# alarm_clock.net
KiCad netlist of a schematic drawn in EAGLE
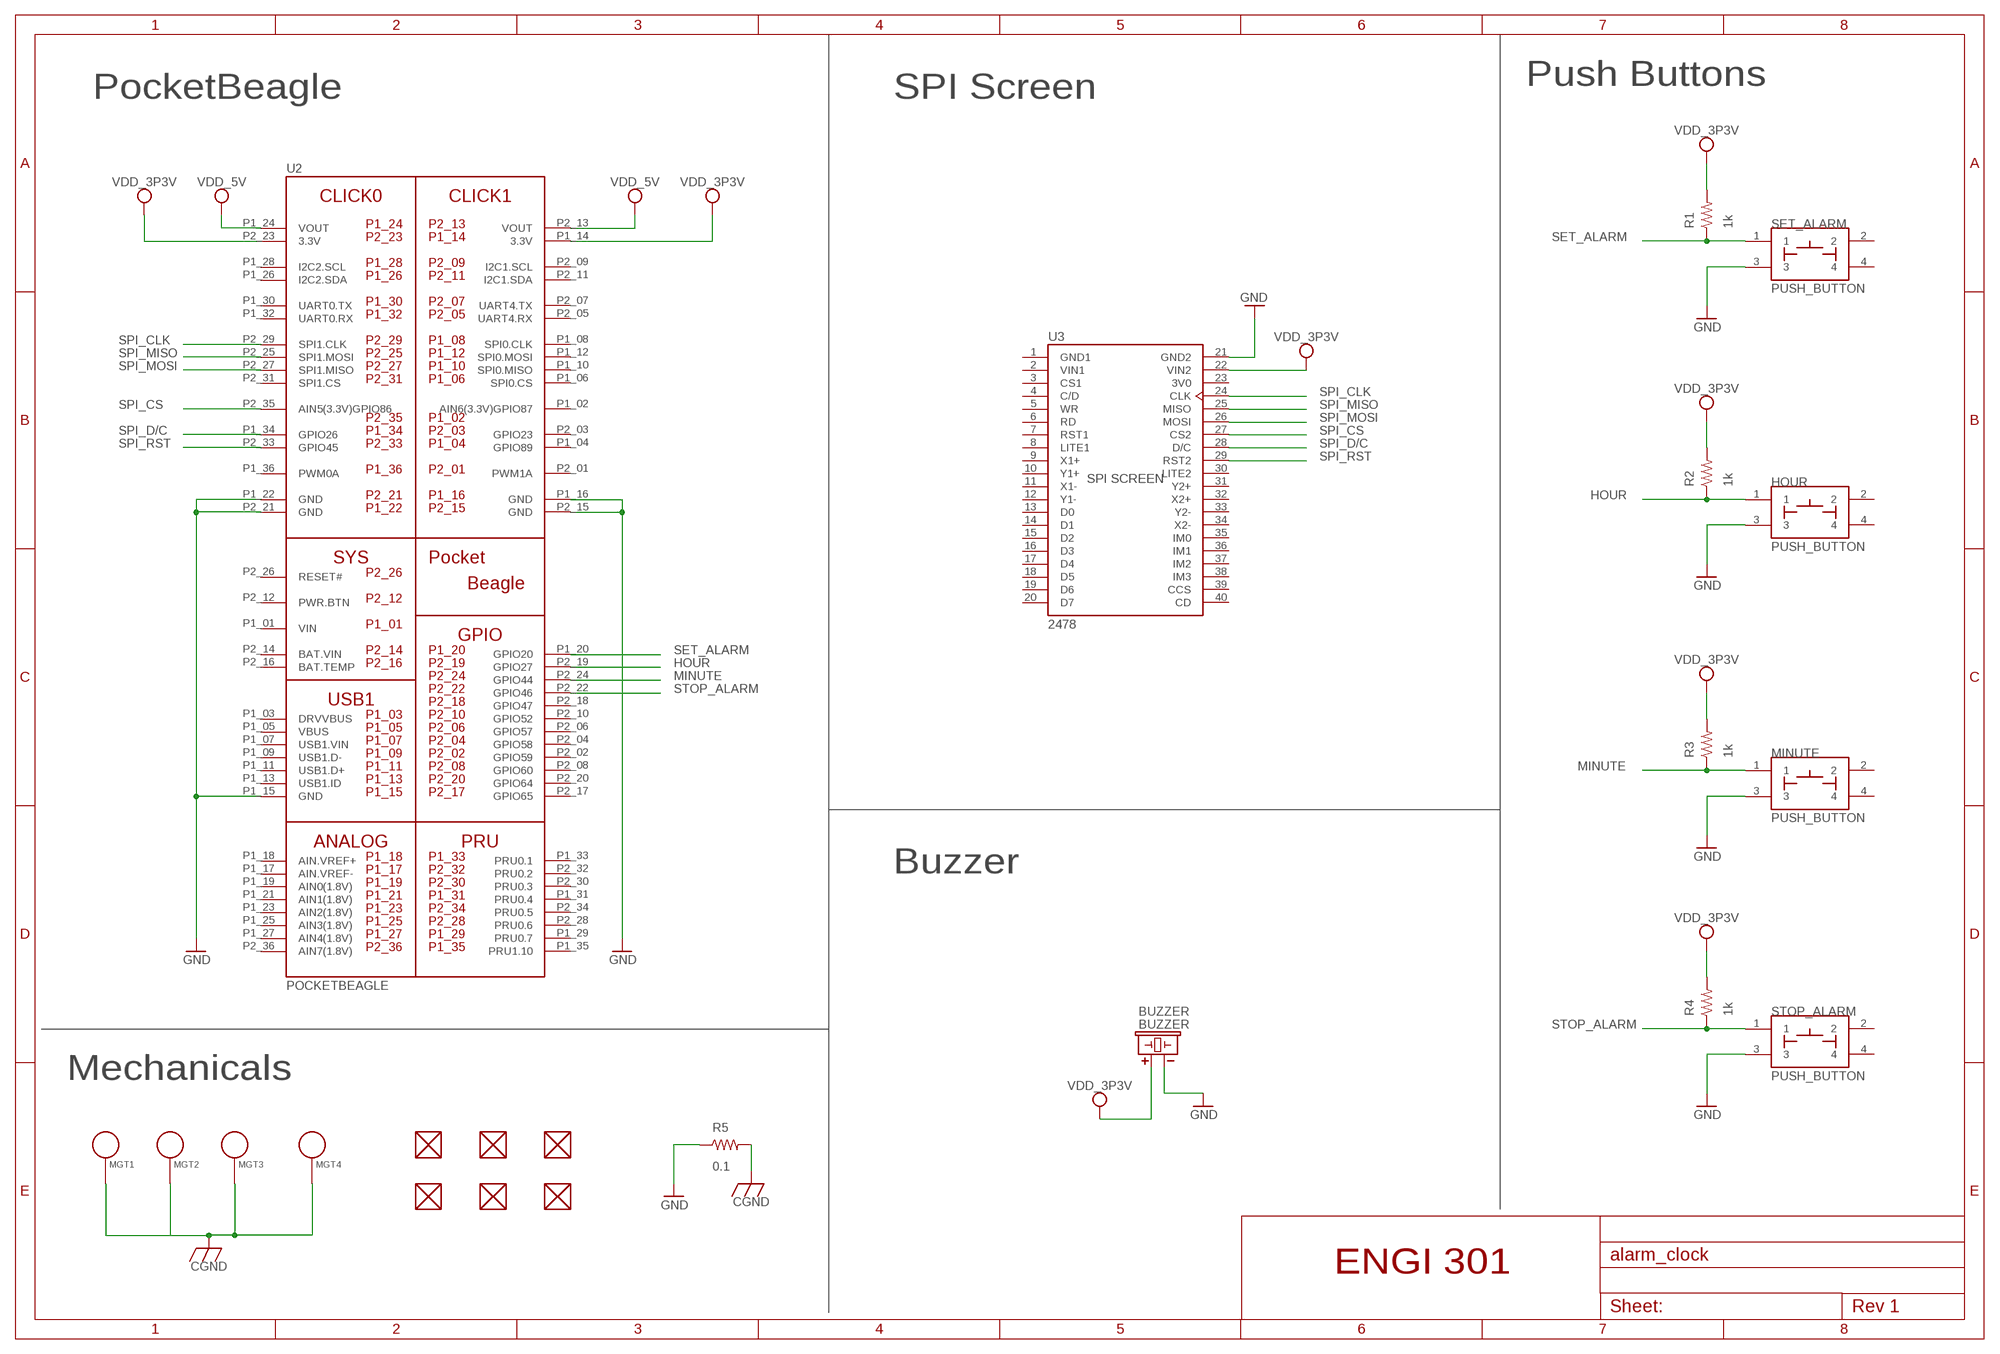
[diagram p0: schematic, sheet 1]

(export (version "E")
  (design (tool "Eeschema 10.0.6"))
  (components
    (comp (ref "BUZZER")
      (value "BUZZER")
      (footprint "eagle-import:BUZZER_6.5MM")
      (libsource (lib "eagle-import") (part "BUZZER"))
    )
    (comp (ref "FUD1")
      (value "FIDUCIAL")
      (footprint "eagle-import:FIDUCIAL_40MIL")
      (libsource (lib "eagle-import") (part "FIDUCIAL"))
    )
    (comp (ref "FUD2")
      (value "FIDUCIAL")
      (footprint "eagle-import:FIDUCIAL_40MIL")
      (libsource (lib "eagle-import") (part "FIDUCIAL"))
    )
    (comp (ref "FUD3")
      (value "FIDUCIAL")
      (footprint "eagle-import:FIDUCIAL_40MIL")
      (libsource (lib "eagle-import") (part "FIDUCIAL"))
    )
    (comp (ref "FUD4")
      (value "FIDUCIAL")
      (footprint "eagle-import:FIDUCIAL_40MIL")
      (libsource (lib "eagle-import") (part "FIDUCIAL"))
    )
    (comp (ref "FUD5")
      (value "FIDUCIAL")
      (footprint "eagle-import:FIDUCIAL_40MIL")
      (libsource (lib "eagle-import") (part "FIDUCIAL"))
    )
    (comp (ref "FUD6")
      (value "FIDUCIAL")
      (footprint "eagle-import:FIDUCIAL_40MIL")
      (libsource (lib "eagle-import") (part "FIDUCIAL"))
    )
    (comp (ref "HOUR")
      (value "PUSH_BUTTON")
      (footprint "eagle-import:BUTTON_12.5MM")
      (libsource (lib "eagle-import") (part "PUSH_BUTTON"))
    )
    (comp (ref "MGT1")
      (value "MOUNTING_HOLE")
      (footprint "eagle-import:MOUNTING_HOLE")
      (libsource (lib "eagle-import") (part "MOUNTING_HOLE"))
    )
    (comp (ref "MGT2")
      (value "MOUNTING_HOLE")
      (footprint "eagle-import:MOUNTING_HOLE")
      (libsource (lib "eagle-import") (part "MOUNTING_HOLE"))
    )
    (comp (ref "MGT3")
      (value "MOUNTING_HOLE")
      (footprint "eagle-import:MOUNTING_HOLE")
      (libsource (lib "eagle-import") (part "MOUNTING_HOLE"))
    )
    (comp (ref "MGT4")
      (value "MOUNTING_HOLE")
      (footprint "eagle-import:MOUNTING_HOLE")
      (libsource (lib "eagle-import") (part "MOUNTING_HOLE"))
    )
    (comp (ref "MINUTE")
      (value "PUSH_BUTTON")
      (footprint "eagle-import:BUTTON_12.5MM")
      (libsource (lib "eagle-import") (part "PUSH_BUTTON"))
    )
    (comp (ref "R1")
      (value "1k")
      (footprint "eagle-import:R0603")
      (libsource (lib "eagle-import") (part "combo_lock_R_R0603"))
    )
    (comp (ref "R2")
      (value "1k")
      (footprint "eagle-import:R0603")
      (libsource (lib "eagle-import") (part "combo_lock_R_R0603"))
    )
    (comp (ref "R3")
      (value "1k")
      (footprint "eagle-import:R0603")
      (libsource (lib "eagle-import") (part "combo_lock_R_R0603"))
    )
    (comp (ref "R4")
      (value "1k")
      (footprint "eagle-import:R0603")
      (libsource (lib "eagle-import") (part "combo_lock_R_R0603"))
    )
    (comp (ref "R5")
      (value "0.1")
      (footprint "eagle-import:R0402")
      (libsource (lib "eagle-import") (part "R_R0402"))
    )
    (comp (ref "SET_ALARM")
      (value "PUSH_BUTTON")
      (footprint "eagle-import:BUTTON_12.5MM")
      (libsource (lib "eagle-import") (part "PUSH_BUTTON"))
    )
    (comp (ref "STOP_ALARM")
      (value "PUSH_BUTTON")
      (footprint "eagle-import:BUTTON_12.5MM")
      (libsource (lib "eagle-import") (part "PUSH_BUTTON"))
    )
    (comp (ref "U2")
      (value "POCKETBEAGLE")
      (footprint "eagle-import:POCKETBEAGLE")
      (libsource (lib "eagle-import") (part "POCKETBEAGLE"))
    )
    (comp (ref "U3")
      (value "2478")
      (footprint "eagle-import:ADAFRUIT_2478")
      (fields (field (name "MF") "Adafruit Industries"))
      (libsource (lib "eagle-import") (part "2478"))
    )
  )
  (nets
    (net (code "1") (name "/BAT.VIN") (class "Default")
      (node (ref "U2") (pin "P2_14") (pinfunction "BAT.VIN_P2_14") (pintype "power_in"))
    )
    (net (code "2") (name "/GND1") (class "Default")
      (node (ref "U3") (pin "1") (pinfunction "GND1_1") (pintype "power_in"))
    )
    (net (code "3") (name "/HOUR") (class "Default")
      (node (ref "HOUR") (pin "1") (pinfunction "1_1") (pintype "bidirectional"))
      (node (ref "R2") (pin "1") (pinfunction "1_1") (pintype "passive"))
      (node (ref "U2") (pin "P2_19") (pinfunction "GPIO27_P2_19") (pintype "bidirectional"))
    )
    (net (code "4") (name "/MINUTE") (class "Default")
      (node (ref "MINUTE") (pin "1") (pinfunction "1_1") (pintype "bidirectional"))
      (node (ref "R3") (pin "1") (pinfunction "1_1") (pintype "passive"))
      (node (ref "U2") (pin "P2_24") (pinfunction "GPIO44_P2_24") (pintype "bidirectional"))
    )
    (net (code "5") (name "/SET_ALARM") (class "Default")
      (node (ref "R1") (pin "1") (pinfunction "1_1") (pintype "passive"))
      (node (ref "SET_ALARM") (pin "1") (pinfunction "1_1") (pintype "bidirectional"))
      (node (ref "U2") (pin "P1_20") (pinfunction "GPIO20_P1_20") (pintype "bidirectional"))
    )
    (net (code "6") (name "/SPI_CLK") (class "Default")
      (node (ref "U2") (pin "P2_29") (pinfunction "SPI1.CLK_P2_29") (pintype "bidirectional"))
      (node (ref "U3") (pin "24") (pinfunction "CLK_24") (pintype "input"))
    )
    (net (code "7") (name "/SPI_CS") (class "Default")
      (node (ref "U2") (pin "P2_35") (pinfunction "AIN5(3.3V)GPIO86_P2_35") (pintype "bidirectional"))
      (node (ref "U3") (pin "27") (pinfunction "CS2_27") (pintype "input"))
    )
    (net (code "8") (name "/SPI_D{slash}C") (class "Default")
      (node (ref "U2") (pin "P1_34") (pinfunction "GPIO26_P1_34") (pintype "bidirectional"))
      (node (ref "U3") (pin "28") (pinfunction "D/C_28") (pintype "input"))
    )
    (net (code "9") (name "/SPI_MISO") (class "Default")
      (node (ref "U2") (pin "P2_25") (pinfunction "SPI1.MOSI_P2_25") (pintype "bidirectional"))
      (node (ref "U3") (pin "25") (pinfunction "MISO_25") (pintype "output"))
    )
    (net (code "10") (name "/SPI_MOSI") (class "Default")
      (node (ref "U2") (pin "P2_27") (pinfunction "SPI1.MISO_P2_27") (pintype "bidirectional"))
      (node (ref "U3") (pin "26") (pinfunction "MOSI_26") (pintype "input"))
    )
    (net (code "11") (name "/SPI_RST") (class "Default")
      (node (ref "U2") (pin "P2_33") (pinfunction "GPIO45_P2_33") (pintype "bidirectional"))
      (node (ref "U3") (pin "29") (pinfunction "RST2_29") (pintype "input"))
    )
    (net (code "12") (name "/STOP_ALARM") (class "Default")
      (node (ref "R4") (pin "1") (pinfunction "1_1") (pintype "passive"))
      (node (ref "STOP_ALARM") (pin "1") (pinfunction "1_1") (pintype "bidirectional"))
      (node (ref "U2") (pin "P2_22") (pinfunction "GPIO46_P2_22") (pintype "bidirectional"))
    )
    (net (code "13") (name "/VIN") (class "Default")
      (node (ref "U2") (pin "P1_01") (pinfunction "VIN_P1_01") (pintype "power_in"))
    )
    (net (code "14") (name "/VIN1") (class "Default")
      (node (ref "U3") (pin "2") (pinfunction "VIN1_2") (pintype "power_in"))
    )
    (net (code "15") (name "CGND") (class "Default")
      (node (ref "MGT1") (pin "P$1") (pinfunction "P$1_P$1") (pintype "bidirectional"))
      (node (ref "MGT2") (pin "P$1") (pinfunction "P$1_P$1") (pintype "bidirectional"))
      (node (ref "MGT3") (pin "P$1") (pinfunction "P$1_P$1") (pintype "bidirectional"))
      (node (ref "MGT4") (pin "P$1") (pinfunction "P$1_P$1") (pintype "bidirectional"))
      (node (ref "R5") (pin "2") (pinfunction "2_2") (pintype "passive"))
    )
    (net (code "16") (name "GND") (class "Default")
      (node (ref "BUZZER") (pin "-") (pinfunction "-_-") (pintype "passive"))
      (node (ref "HOUR") (pin "3") (pinfunction "3_3") (pintype "bidirectional"))
      (node (ref "MINUTE") (pin "3") (pinfunction "3_3") (pintype "bidirectional"))
      (node (ref "R5") (pin "1") (pinfunction "1_1") (pintype "passive"))
      (node (ref "SET_ALARM") (pin "3") (pinfunction "3_3") (pintype "bidirectional"))
      (node (ref "STOP_ALARM") (pin "3") (pinfunction "3_3") (pintype "bidirectional"))
      (node (ref "U2") (pin "P1_15") (pinfunction "GND_P1_15") (pintype "bidirectional"))
      (node (ref "U2") (pin "P1_16") (pinfunction "GND_P1_16") (pintype "power_in"))
      (node (ref "U2") (pin "P1_22") (pinfunction "GND_P1_22") (pintype "power_in"))
      (node (ref "U2") (pin "P2_15") (pinfunction "GND_P2_15") (pintype "power_in"))
      (node (ref "U2") (pin "P2_21") (pinfunction "GND_P2_21") (pintype "power_in"))
      (node (ref "U3") (pin "21") (pinfunction "GND2_21") (pintype "power_in"))
    )
    (net (code "17") (name "VDD_3P3V") (class "Default")
      (node (ref "BUZZER") (pin "+") (pinfunction "+_+") (pintype "passive"))
      (node (ref "R1") (pin "2") (pinfunction "2_2") (pintype "passive"))
      (node (ref "R2") (pin "2") (pinfunction "2_2") (pintype "passive"))
      (node (ref "R3") (pin "2") (pinfunction "2_2") (pintype "passive"))
      (node (ref "R4") (pin "2") (pinfunction "2_2") (pintype "passive"))
      (node (ref "U2") (pin "P1_14") (pinfunction "3.3V_P1_14") (pintype "power_in"))
      (node (ref "U2") (pin "P2_23") (pinfunction "3.3V_P2_23") (pintype "power_in"))
      (node (ref "U3") (pin "22") (pinfunction "VIN2_22") (pintype "power_in"))
    )
    (net (code "18") (name "VDD_5V") (class "Default")
      (node (ref "U2") (pin "P1_24") (pinfunction "VOUT_P1_24") (pintype "power_in"))
      (node (ref "U2") (pin "P2_13") (pinfunction "VOUT_P2_13") (pintype "power_in"))
    )
    (net (code "19") (name "unconnected-(FUD1-PadP$1)") (class "Default")
      (node (ref "FUD1") (pin "P$1") (pinfunction "P$1_P$1") (pintype "no_connect"))
    )
    (net (code "20") (name "unconnected-(FUD2-PadP$1)") (class "Default")
      (node (ref "FUD2") (pin "P$1") (pinfunction "P$1_P$1") (pintype "no_connect"))
    )
    (net (code "21") (name "unconnected-(FUD3-PadP$1)") (class "Default")
      (node (ref "FUD3") (pin "P$1") (pinfunction "P$1_P$1") (pintype "no_connect"))
    )
    (net (code "22") (name "unconnected-(FUD4-PadP$1)") (class "Default")
      (node (ref "FUD4") (pin "P$1") (pinfunction "P$1_P$1") (pintype "no_connect"))
    )
    (net (code "23") (name "unconnected-(FUD5-PadP$1)") (class "Default")
      (node (ref "FUD5") (pin "P$1") (pinfunction "P$1_P$1") (pintype "no_connect"))
    )
    (net (code "24") (name "unconnected-(FUD6-PadP$1)") (class "Default")
      (node (ref "FUD6") (pin "P$1") (pinfunction "P$1_P$1") (pintype "no_connect"))
    )
    (net (code "25") (name "unconnected-(HOUR-Pad2)") (class "Default")
      (node (ref "HOUR") (pin "2") (pinfunction "2_2") (pintype "bidirectional"))
    )
    (net (code "26") (name "unconnected-(HOUR-Pad4)") (class "Default")
      (node (ref "HOUR") (pin "4") (pinfunction "4_4") (pintype "bidirectional"))
    )
    (net (code "27") (name "unconnected-(MINUTE-Pad2)") (class "Default")
      (node (ref "MINUTE") (pin "2") (pinfunction "2_2") (pintype "bidirectional"))
    )
    (net (code "28") (name "unconnected-(MINUTE-Pad4)") (class "Default")
      (node (ref "MINUTE") (pin "4") (pinfunction "4_4") (pintype "bidirectional"))
    )
    (net (code "29") (name "unconnected-(SET_ALARM-Pad2)") (class "Default")
      (node (ref "SET_ALARM") (pin "2") (pinfunction "2_2") (pintype "bidirectional"))
    )
    (net (code "30") (name "unconnected-(SET_ALARM-Pad4)") (class "Default")
      (node (ref "SET_ALARM") (pin "4") (pinfunction "4_4") (pintype "bidirectional"))
    )
    (net (code "31") (name "unconnected-(STOP_ALARM-Pad2)") (class "Default")
      (node (ref "STOP_ALARM") (pin "2") (pinfunction "2_2") (pintype "bidirectional"))
    )
    (net (code "32") (name "unconnected-(STOP_ALARM-Pad4)") (class "Default")
      (node (ref "STOP_ALARM") (pin "4") (pinfunction "4_4") (pintype "bidirectional"))
    )
    (net (code "33") (name "unconnected-(U2-AIN.VREF+-PadP1_18)") (class "Default")
      (node (ref "U2") (pin "P1_18") (pinfunction "AIN.VREF+_P1_18") (pintype "input"))
    )
    (net (code "34") (name "unconnected-(U2-AIN.VREF--PadP1_17)") (class "Default")
      (node (ref "U2") (pin "P1_17") (pinfunction "AIN.VREF-_P1_17") (pintype "input"))
    )
    (net (code "35") (name "unconnected-(U2-AIN0(1.8V)-PadP1_19)") (class "Default")
      (node (ref "U2") (pin "P1_19") (pinfunction "AIN0(1.8V)_P1_19") (pintype "input"))
    )
    (net (code "36") (name "unconnected-(U2-AIN1(1.8V)-PadP1_21)") (class "Default")
      (node (ref "U2") (pin "P1_21") (pinfunction "AIN1(1.8V)_P1_21") (pintype "input"))
    )
    (net (code "37") (name "unconnected-(U2-AIN2(1.8V)-PadP1_23)") (class "Default")
      (node (ref "U2") (pin "P1_23") (pinfunction "AIN2(1.8V)_P1_23") (pintype "input"))
    )
    (net (code "38") (name "unconnected-(U2-AIN3(1.8V)-PadP1_25)") (class "Default")
      (node (ref "U2") (pin "P1_25") (pinfunction "AIN3(1.8V)_P1_25") (pintype "input"))
    )
    (net (code "39") (name "unconnected-(U2-AIN4(1.8V)-PadP1_27)") (class "Default")
      (node (ref "U2") (pin "P1_27") (pinfunction "AIN4(1.8V)_P1_27") (pintype "input"))
    )
    (net (code "40") (name "unconnected-(U2-AIN6(3.3V)GPIO87-PadP1_02)") (class "Default")
      (node (ref "U2") (pin "P1_02") (pinfunction "AIN6(3.3V)GPIO87_P1_02") (pintype "bidirectional"))
    )
    (net (code "41") (name "unconnected-(U2-AIN7(1.8V)-PadP2_36)") (class "Default")
      (node (ref "U2") (pin "P2_36") (pinfunction "AIN7(1.8V)_P2_36") (pintype "input"))
    )
    (net (code "42") (name "unconnected-(U2-BAT.TEMP-PadP2_16)") (class "Default")
      (node (ref "U2") (pin "P2_16") (pinfunction "BAT.TEMP_P2_16") (pintype "input"))
    )
    (net (code "43") (name "unconnected-(U2-DRVVBUS-PadP1_03)") (class "Default")
      (node (ref "U2") (pin "P1_03") (pinfunction "DRVVBUS_P1_03") (pintype "bidirectional"))
    )
    (net (code "44") (name "unconnected-(U2-GPIO23-PadP2_03)") (class "Default")
      (node (ref "U2") (pin "P2_03") (pinfunction "GPIO23_P2_03") (pintype "bidirectional"))
    )
    (net (code "45") (name "unconnected-(U2-GPIO47-PadP2_18)") (class "Default")
      (node (ref "U2") (pin "P2_18") (pinfunction "GPIO47_P2_18") (pintype "bidirectional"))
    )
    (net (code "46") (name "unconnected-(U2-GPIO52-PadP2_10)") (class "Default")
      (node (ref "U2") (pin "P2_10") (pinfunction "GPIO52_P2_10") (pintype "bidirectional"))
    )
    (net (code "47") (name "unconnected-(U2-GPIO57-PadP2_06)") (class "Default")
      (node (ref "U2") (pin "P2_06") (pinfunction "GPIO57_P2_06") (pintype "bidirectional"))
    )
    (net (code "48") (name "unconnected-(U2-GPIO58-PadP2_04)") (class "Default")
      (node (ref "U2") (pin "P2_04") (pinfunction "GPIO58_P2_04") (pintype "bidirectional"))
    )
    (net (code "49") (name "unconnected-(U2-GPIO59-PadP2_02)") (class "Default")
      (node (ref "U2") (pin "P2_02") (pinfunction "GPIO59_P2_02") (pintype "bidirectional"))
    )
    (net (code "50") (name "unconnected-(U2-GPIO60-PadP2_08)") (class "Default")
      (node (ref "U2") (pin "P2_08") (pinfunction "GPIO60_P2_08") (pintype "bidirectional"))
    )
    (net (code "51") (name "unconnected-(U2-GPIO64-PadP2_20)") (class "Default")
      (node (ref "U2") (pin "P2_20") (pinfunction "GPIO64_P2_20") (pintype "bidirectional"))
    )
    (net (code "52") (name "unconnected-(U2-GPIO65-PadP2_17)") (class "Default")
      (node (ref "U2") (pin "P2_17") (pinfunction "GPIO65_P2_17") (pintype "bidirectional"))
    )
    (net (code "53") (name "unconnected-(U2-GPIO89-PadP1_04)") (class "Default")
      (node (ref "U2") (pin "P1_04") (pinfunction "GPIO89_P1_04") (pintype "bidirectional"))
    )
    (net (code "54") (name "unconnected-(U2-I2C1.SCL-PadP2_09)") (class "Default")
      (node (ref "U2") (pin "P2_09") (pinfunction "I2C1.SCL_P2_09") (pintype "bidirectional"))
    )
    (net (code "55") (name "unconnected-(U2-I2C1.SDA-PadP2_11)") (class "Default")
      (node (ref "U2") (pin "P2_11") (pinfunction "I2C1.SDA_P2_11") (pintype "bidirectional"))
    )
    (net (code "56") (name "unconnected-(U2-I2C2.SCL-PadP1_28)") (class "Default")
      (node (ref "U2") (pin "P1_28") (pinfunction "I2C2.SCL_P1_28") (pintype "bidirectional"))
    )
    (net (code "57") (name "unconnected-(U2-I2C2.SDA-PadP1_26)") (class "Default")
      (node (ref "U2") (pin "P1_26") (pinfunction "I2C2.SDA_P1_26") (pintype "bidirectional"))
    )
    (net (code "58") (name "unconnected-(U2-PRU0.1-PadP1_33)") (class "Default")
      (node (ref "U2") (pin "P1_33") (pinfunction "PRU0.1_P1_33") (pintype "bidirectional"))
    )
    (net (code "59") (name "unconnected-(U2-PRU0.2-PadP2_32)") (class "Default")
      (node (ref "U2") (pin "P2_32") (pinfunction "PRU0.2_P2_32") (pintype "bidirectional"))
    )
    (net (code "60") (name "unconnected-(U2-PRU0.3-PadP2_30)") (class "Default")
      (node (ref "U2") (pin "P2_30") (pinfunction "PRU0.3_P2_30") (pintype "bidirectional"))
    )
    (net (code "61") (name "unconnected-(U2-PRU0.4-PadP1_31)") (class "Default")
      (node (ref "U2") (pin "P1_31") (pinfunction "PRU0.4_P1_31") (pintype "bidirectional"))
    )
    (net (code "62") (name "unconnected-(U2-PRU0.5-PadP2_34)") (class "Default")
      (node (ref "U2") (pin "P2_34") (pinfunction "PRU0.5_P2_34") (pintype "bidirectional"))
    )
    (net (code "63") (name "unconnected-(U2-PRU0.6-PadP2_28)") (class "Default")
      (node (ref "U2") (pin "P2_28") (pinfunction "PRU0.6_P2_28") (pintype "bidirectional"))
    )
    (net (code "64") (name "unconnected-(U2-PRU0.7-PadP1_29)") (class "Default")
      (node (ref "U2") (pin "P1_29") (pinfunction "PRU0.7_P1_29") (pintype "bidirectional"))
    )
    (net (code "65") (name "unconnected-(U2-PRU1.10-PadP1_35)") (class "Default")
      (node (ref "U2") (pin "P1_35") (pinfunction "PRU1.10_P1_35") (pintype "bidirectional"))
    )
    (net (code "66") (name "unconnected-(U2-PWM0A-PadP1_36)") (class "Default")
      (node (ref "U2") (pin "P1_36") (pinfunction "PWM0A_P1_36") (pintype "bidirectional"))
    )
    (net (code "67") (name "unconnected-(U2-PWM1A-PadP2_01)") (class "Default")
      (node (ref "U2") (pin "P2_01") (pinfunction "PWM1A_P2_01") (pintype "bidirectional"))
    )
    (net (code "68") (name "unconnected-(U2-PWR.BTN-PadP2_12)") (class "Default")
      (node (ref "U2") (pin "P2_12") (pinfunction "PWR.BTN_P2_12") (pintype "input"))
    )
    (net (code "69") (name "unconnected-(U2-RESET#-PadP2_26)") (class "Default")
      (node (ref "U2") (pin "P2_26") (pinfunction "RESET#_P2_26") (pintype "input"))
    )
    (net (code "70") (name "unconnected-(U2-SPI0.CLK-PadP1_08)") (class "Default")
      (node (ref "U2") (pin "P1_08") (pinfunction "SPI0.CLK_P1_08") (pintype "bidirectional"))
    )
    (net (code "71") (name "unconnected-(U2-SPI0.CS-PadP1_06)") (class "Default")
      (node (ref "U2") (pin "P1_06") (pinfunction "SPI0.CS_P1_06") (pintype "bidirectional"))
    )
    (net (code "72") (name "unconnected-(U2-SPI0.MISO-PadP1_10)") (class "Default")
      (node (ref "U2") (pin "P1_10") (pinfunction "SPI0.MISO_P1_10") (pintype "bidirectional"))
    )
    (net (code "73") (name "unconnected-(U2-SPI0.MOSI-PadP1_12)") (class "Default")
      (node (ref "U2") (pin "P1_12") (pinfunction "SPI0.MOSI_P1_12") (pintype "bidirectional"))
    )
    (net (code "74") (name "unconnected-(U2-SPI1.CS-PadP2_31)") (class "Default")
      (node (ref "U2") (pin "P2_31") (pinfunction "SPI1.CS_P2_31") (pintype "bidirectional"))
    )
    (net (code "75") (name "unconnected-(U2-UART0.RX-PadP1_32)") (class "Default")
      (node (ref "U2") (pin "P1_32") (pinfunction "UART0.RX_P1_32") (pintype "bidirectional"))
    )
    (net (code "76") (name "unconnected-(U2-UART0.TX-PadP1_30)") (class "Default")
      (node (ref "U2") (pin "P1_30") (pinfunction "UART0.TX_P1_30") (pintype "bidirectional"))
    )
    (net (code "77") (name "unconnected-(U2-UART4.RX-PadP2_05)") (class "Default")
      (node (ref "U2") (pin "P2_05") (pinfunction "UART4.RX_P2_05") (pintype "bidirectional"))
    )
    (net (code "78") (name "unconnected-(U2-UART4.TX-PadP2_07)") (class "Default")
      (node (ref "U2") (pin "P2_07") (pinfunction "UART4.TX_P2_07") (pintype "bidirectional"))
    )
    (net (code "79") (name "unconnected-(U2-USB1.D+-PadP1_11)") (class "Default")
      (node (ref "U2") (pin "P1_11") (pinfunction "USB1.D+_P1_11") (pintype "bidirectional"))
    )
    (net (code "80") (name "unconnected-(U2-USB1.D--PadP1_09)") (class "Default")
      (node (ref "U2") (pin "P1_09") (pinfunction "USB1.D-_P1_09") (pintype "bidirectional"))
    )
    (net (code "81") (name "unconnected-(U2-USB1.ID-PadP1_13)") (class "Default")
      (node (ref "U2") (pin "P1_13") (pinfunction "USB1.ID_P1_13") (pintype "bidirectional"))
    )
    (net (code "82") (name "unconnected-(U2-USB1.VIN-PadP1_07)") (class "Default")
      (node (ref "U2") (pin "P1_07") (pinfunction "USB1.VIN_P1_07") (pintype "bidirectional"))
    )
    (net (code "83") (name "unconnected-(U2-VBUS-PadP1_05)") (class "Default")
      (node (ref "U2") (pin "P1_05") (pinfunction "VBUS_P1_05") (pintype "bidirectional"))
    )
    (net (code "84") (name "unconnected-(U3-3V0-Pad23)") (class "Default")
      (node (ref "U3") (pin "23") (pinfunction "3V0_23") (pintype "output"))
    )
    (net (code "85") (name "unconnected-(U3-CCS-Pad39)") (class "Default")
      (node (ref "U3") (pin "39") (pinfunction "CCS_39") (pintype "input"))
    )
    (net (code "86") (name "unconnected-(U3-CD-Pad40)") (class "Default")
      (node (ref "U3") (pin "40") (pinfunction "CD_40") (pintype "output"))
    )
    (net (code "87") (name "unconnected-(U3-CS1-Pad3)") (class "Default")
      (node (ref "U3") (pin "3") (pinfunction "CS1_3") (pintype "input"))
    )
    (net (code "88") (name "unconnected-(U3-C{slash}D-Pad4)") (class "Default")
      (node (ref "U3") (pin "4") (pinfunction "C/D_4") (pintype "input"))
    )
    (net (code "89") (name "unconnected-(U3-D0-Pad13)") (class "Default")
      (node (ref "U3") (pin "13") (pinfunction "D0_13") (pintype "bidirectional"))
    )
    (net (code "90") (name "unconnected-(U3-D1-Pad14)") (class "Default")
      (node (ref "U3") (pin "14") (pinfunction "D1_14") (pintype "bidirectional"))
    )
    (net (code "91") (name "unconnected-(U3-D2-Pad15)") (class "Default")
      (node (ref "U3") (pin "15") (pinfunction "D2_15") (pintype "bidirectional"))
    )
    (net (code "92") (name "unconnected-(U3-D3-Pad16)") (class "Default")
      (node (ref "U3") (pin "16") (pinfunction "D3_16") (pintype "bidirectional"))
    )
    (net (code "93") (name "unconnected-(U3-D4-Pad17)") (class "Default")
      (node (ref "U3") (pin "17") (pinfunction "D4_17") (pintype "bidirectional"))
    )
    (net (code "94") (name "unconnected-(U3-D5-Pad18)") (class "Default")
      (node (ref "U3") (pin "18") (pinfunction "D5_18") (pintype "bidirectional"))
    )
    (net (code "95") (name "unconnected-(U3-D6-Pad19)") (class "Default")
      (node (ref "U3") (pin "19") (pinfunction "D6_19") (pintype "bidirectional"))
    )
    (net (code "96") (name "unconnected-(U3-D7-Pad20)") (class "Default")
      (node (ref "U3") (pin "20") (pinfunction "D7_20") (pintype "bidirectional"))
    )
    (net (code "97") (name "unconnected-(U3-IM0-Pad35)") (class "Default")
      (node (ref "U3") (pin "35") (pinfunction "IM0_35") (pintype "input"))
    )
    (net (code "98") (name "unconnected-(U3-IM1-Pad36)") (class "Default")
      (node (ref "U3") (pin "36") (pinfunction "IM1_36") (pintype "input"))
    )
    (net (code "99") (name "unconnected-(U3-IM2-Pad37)") (class "Default")
      (node (ref "U3") (pin "37") (pinfunction "IM2_37") (pintype "input"))
    )
    (net (code "100") (name "unconnected-(U3-IM3-Pad38)") (class "Default")
      (node (ref "U3") (pin "38") (pinfunction "IM3_38") (pintype "input"))
    )
    (net (code "101") (name "unconnected-(U3-LITE1-Pad8)") (class "Default")
      (node (ref "U3") (pin "8") (pinfunction "LITE1_8") (pintype "input"))
    )
    (net (code "102") (name "unconnected-(U3-LITE2-Pad30)") (class "Default")
      (node (ref "U3") (pin "30") (pinfunction "LITE2_30") (pintype "input"))
    )
    (net (code "103") (name "unconnected-(U3-RD-Pad6)") (class "Default")
      (node (ref "U3") (pin "6") (pinfunction "RD_6") (pintype "input"))
    )
    (net (code "104") (name "unconnected-(U3-RST1-Pad7)") (class "Default")
      (node (ref "U3") (pin "7") (pinfunction "RST1_7") (pintype "input"))
    )
    (net (code "105") (name "unconnected-(U3-WR-Pad5)") (class "Default")
      (node (ref "U3") (pin "5") (pinfunction "WR_5") (pintype "input"))
    )
    (net (code "106") (name "unconnected-(U3-X1+-Pad9)") (class "Default")
      (node (ref "U3") (pin "9") (pinfunction "X1+_9") (pintype "output"))
    )
    (net (code "107") (name "unconnected-(U3-X1--Pad11)") (class "Default")
      (node (ref "U3") (pin "11") (pinfunction "X1-_11") (pintype "output"))
    )
    (net (code "108") (name "unconnected-(U3-X2+-Pad32)") (class "Default")
      (node (ref "U3") (pin "32") (pinfunction "X2+_32") (pintype "output"))
    )
    (net (code "109") (name "unconnected-(U3-X2--Pad34)") (class "Default")
      (node (ref "U3") (pin "34") (pinfunction "X2-_34") (pintype "output"))
    )
    (net (code "110") (name "unconnected-(U3-Y1+-Pad10)") (class "Default")
      (node (ref "U3") (pin "10") (pinfunction "Y1+_10") (pintype "output"))
    )
    (net (code "111") (name "unconnected-(U3-Y1--Pad12)") (class "Default")
      (node (ref "U3") (pin "12") (pinfunction "Y1-_12") (pintype "output"))
    )
    (net (code "112") (name "unconnected-(U3-Y2+-Pad31)") (class "Default")
      (node (ref "U3") (pin "31") (pinfunction "Y2+_31") (pintype "output"))
    )
    (net (code "113") (name "unconnected-(U3-Y2--Pad33)") (class "Default")
      (node (ref "U3") (pin "33") (pinfunction "Y2-_33") (pintype "output"))
    )
  )
)
